# L298N.net
KiCad netlist of a schematic drawn in Altium Designer
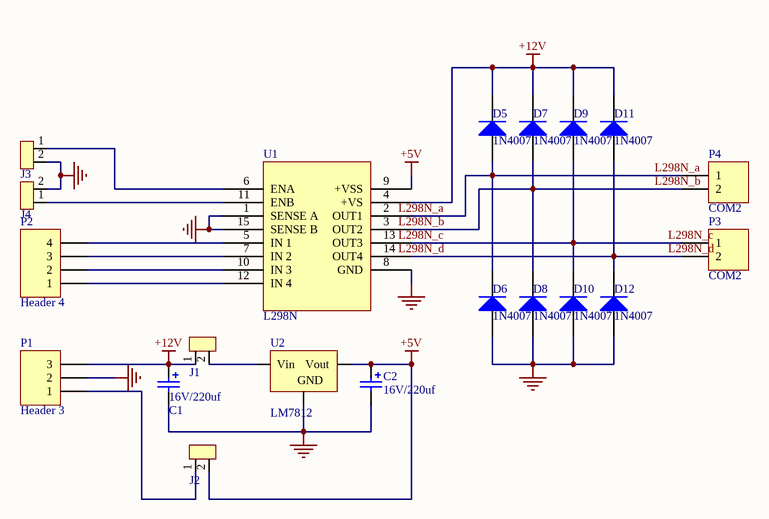
[diagram p0: L298N.SchDoc]

(export (version "E")
  (design (tool "Eeschema 10.0.6"))
  (components
    (comp (ref "C1")
      (value "16V/220uf")
      (footprint "RB5/8")
      (description "Polarized Capacitor (Radial)")
      (fields (field (name "PUBLISHER") "Altium Limited"))
      (libsource (lib "MY COM new") (part "RB"))
    )
    (comp (ref "C2")
      (value "16V/220uf")
      (footprint "RB5/8")
      (description "Polarized Capacitor (Radial)")
      (fields (field (name "PUBLISHER") "Altium Limited"))
      (libsource (lib "MY COM new") (part "RB"))
    )
    (comp (ref "D5")
      (value "1N4007")
      (footprint "Diode0.3")
      (description "1 Amp General Purpose Rectifier")
      (fields (field (name "PUBLISHER") "Altium Limited"))
      (libsource (lib "Miscellaneous Devices") (part "Diode 1N4007"))
    )
    (comp (ref "D6")
      (value "1N4007")
      (footprint "Diode0.3")
      (description "1 Amp General Purpose Rectifier")
      (fields (field (name "PUBLISHER") "Altium Limited"))
      (libsource (lib "Miscellaneous Devices") (part "Diode 1N4007"))
    )
    (comp (ref "D7")
      (value "1N4007")
      (footprint "Diode0.3")
      (description "1 Amp General Purpose Rectifier")
      (fields (field (name "PUBLISHER") "Altium Limited"))
      (libsource (lib "Miscellaneous Devices") (part "Diode 1N4007"))
    )
    (comp (ref "D8")
      (value "1N4007")
      (footprint "Diode0.3")
      (description "1 Amp General Purpose Rectifier")
      (fields (field (name "PUBLISHER") "Altium Limited"))
      (libsource (lib "Miscellaneous Devices") (part "Diode 1N4007"))
    )
    (comp (ref "D9")
      (value "1N4007")
      (footprint "Diode0.3")
      (description "1 Amp General Purpose Rectifier")
      (fields (field (name "PUBLISHER") "Altium Limited"))
      (libsource (lib "Miscellaneous Devices") (part "Diode 1N4007"))
    )
    (comp (ref "D10")
      (value "1N4007")
      (footprint "Diode0.3")
      (description "1 Amp General Purpose Rectifier")
      (fields (field (name "PUBLISHER") "Altium Limited"))
      (libsource (lib "Miscellaneous Devices") (part "Diode 1N4007"))
    )
    (comp (ref "D11")
      (value "1N4007")
      (footprint "Diode0.3")
      (description "1 Amp General Purpose Rectifier")
      (fields (field (name "PUBLISHER") "Altium Limited"))
      (libsource (lib "Miscellaneous Devices") (part "Diode 1N4007"))
    )
    (comp (ref "D12")
      (value "1N4007")
      (footprint "Diode0.3")
      (description "1 Amp General Purpose Rectifier")
      (fields (field (name "PUBLISHER") "Altium Limited"))
      (libsource (lib "Miscellaneous Devices") (part "Diode 1N4007"))
    )
    (comp (ref "J1") (value "~") (footprint "SIP2") (libsource (lib "") (part "CN2_1")))
    (comp (ref "J2") (value "CN2") (footprint "SIP2") (libsource (lib "") (part "CN2_1")))
    (comp (ref "J3") (value "~") (footprint "XH2.54-2P") (libsource (lib "") (part "CN2_2")))
    (comp (ref "J4") (value "~") (footprint "XH2.54-2P") (libsource (lib "MY COM new") (part "CN2")))
    (comp (ref "P1")
      (value "Header 3")
      (footprint "XH5.08-3P")
      (description "Header, 3-Pin")
      (fields (field (name "PUBLISHER") "Altium Limited"))
      (libsource (lib "Miscellaneous Connectors") (part "Header 3"))
    )
    (comp (ref "P2")
      (value "Header 4")
      (footprint "XH2.54-4P")
      (description "Header, 4-Pin")
      (fields (field (name "PUBLISHER") "Altium Limited"))
      (libsource (lib "Miscellaneous Connectors") (part "Header 4"))
    )
    (comp (ref "P3")
      (value "COM2")
      (footprint "XH5.08-2P")
      (description "Header, 2-Pin")
      (fields (field (name "PUBLISHER") "Altium Limited"))
      (libsource (lib "Miscellaneous Connectors") (part "Header 2"))
    )
    (comp (ref "P4")
      (value "COM2")
      (footprint "XH5.08-2P")
      (description "Header, 2-Pin")
      (fields (field (name "PUBLISHER") "Altium Limited"))
      (libsource (lib "Miscellaneous Connectors") (part "Header 2"))
    )
    (comp (ref "U1") (value "L298N") (footprint "L298N散热片") (libsource (lib "KU1") (part "L298N")))
    (comp (ref "U2")
      (value "LM7812")
      (footprint "TO-220")
      (description "Voltage Regulator")
      (fields (field (name "PUBLISHER") "Altium Limited"))
      (libsource (lib "MY COM new") (part "Voltage regulator"))
    )
  )
  (nets
    (net (code "1") (name "+5V") (class "Default")
      (node (ref "C2") (pin "1") (pinfunction "1_1") (pintype "passive"))
      (node (ref "J2") (pin "2") (pintype "passive"))
      (node (ref "U1") (pin "9") (pinfunction "+VSS_9") (pintype "passive"))
      (node (ref "U2") (pin "3") (pinfunction "Vout_3") (pintype "passive"))
    )
    (net (code "2") (name "+12V") (class "Default")
      (node (ref "C1") (pin "1") (pinfunction "1_1") (pintype "passive"))
      (node (ref "D11") (pin "2") (pinfunction "K_2") (pintype "passive"))
      (node (ref "D5") (pin "2") (pinfunction "K_2") (pintype "passive"))
      (node (ref "D7") (pin "2") (pinfunction "K_2") (pintype "passive"))
      (node (ref "D9") (pin "2") (pinfunction "K_2") (pintype "passive"))
      (node (ref "J1") (pin "1") (pintype "passive"))
      (node (ref "P1") (pin "3") (pinfunction "3_3") (pintype "passive"))
      (node (ref "U1") (pin "4") (pinfunction "+VS_4") (pintype "passive"))
    )
    (net (code "3") (name "/L298N_a") (class "Default")
      (node (ref "D5") (pin "1") (pinfunction "A_1") (pintype "passive"))
      (node (ref "D6") (pin "2") (pinfunction "K_2") (pintype "passive"))
      (node (ref "P4") (pin "1") (pinfunction "1_1") (pintype "passive"))
      (node (ref "U1") (pin "2") (pinfunction "OUT1_2") (pintype "passive"))
    )
    (net (code "4") (name "/L298N_b") (class "Default")
      (node (ref "D7") (pin "1") (pinfunction "A_1") (pintype "passive"))
      (node (ref "D8") (pin "2") (pinfunction "K_2") (pintype "passive"))
      (node (ref "P4") (pin "2") (pinfunction "2_2") (pintype "passive"))
      (node (ref "U1") (pin "3") (pinfunction "OUT2_3") (pintype "passive"))
    )
    (net (code "5") (name "/L298N_c") (class "Default")
      (node (ref "D10") (pin "2") (pinfunction "K_2") (pintype "passive"))
      (node (ref "D9") (pin "1") (pinfunction "A_1") (pintype "passive"))
      (node (ref "P3") (pin "1") (pinfunction "1_1") (pintype "passive"))
      (node (ref "U1") (pin "13") (pinfunction "OUT3_13") (pintype "passive"))
    )
    (net (code "6") (name "/L298N_d") (class "Default")
      (node (ref "D11") (pin "1") (pinfunction "A_1") (pintype "passive"))
      (node (ref "D12") (pin "2") (pinfunction "K_2") (pintype "passive"))
      (node (ref "P3") (pin "2") (pinfunction "2_2") (pintype "passive"))
      (node (ref "U1") (pin "14") (pinfunction "OUT4_14") (pintype "passive"))
    )
    (net (code "7") (name "GND") (class "Default")
      (node (ref "C1") (pin "2") (pinfunction "2_2") (pintype "passive"))
      (node (ref "C2") (pin "2") (pinfunction "2_2") (pintype "passive"))
      (node (ref "D10") (pin "1") (pinfunction "A_1") (pintype "passive"))
      (node (ref "D12") (pin "1") (pinfunction "A_1") (pintype "passive"))
      (node (ref "D6") (pin "1") (pinfunction "A_1") (pintype "passive"))
      (node (ref "D8") (pin "1") (pinfunction "A_1") (pintype "passive"))
      (node (ref "J3") (pin "2") (pintype "passive"))
      (node (ref "J4") (pin "2") (pintype "passive"))
      (node (ref "P1") (pin "2") (pinfunction "2_2") (pintype "passive"))
      (node (ref "U1") (pin "1") (pinfunction "SENSE_A_1") (pintype "passive"))
      (node (ref "U1") (pin "15") (pinfunction "SENSE_B_15") (pintype "passive"))
      (node (ref "U1") (pin "8") (pinfunction "GND_8") (pintype "passive"))
      (node (ref "U2") (pin "2") (pinfunction "GND_2") (pintype "passive"))
    )
    (net (code "8") (name "Net-(J2-Pad1)") (class "Default")
      (node (ref "J2") (pin "1") (pintype "passive"))
      (node (ref "P1") (pin "1") (pinfunction "1_1") (pintype "passive"))
    )
    (net (code "9") (name "Net-(U1-ENA)") (class "Default")
      (node (ref "J3") (pin "1") (pintype "passive"))
      (node (ref "U1") (pin "6") (pinfunction "ENA_6") (pintype "passive"))
    )
    (net (code "10") (name "Net-(U1-ENB)") (class "Default")
      (node (ref "J4") (pin "1") (pintype "passive"))
      (node (ref "U1") (pin "11") (pinfunction "ENB_11") (pintype "passive"))
    )
    (net (code "11") (name "Net-(U1-IN_1)") (class "Default")
      (node (ref "P2") (pin "4") (pinfunction "4_4") (pintype "passive"))
      (node (ref "U1") (pin "5") (pinfunction "IN_1_5") (pintype "passive"))
    )
    (net (code "12") (name "Net-(U1-IN_2)") (class "Default")
      (node (ref "P2") (pin "3") (pinfunction "3_3") (pintype "passive"))
      (node (ref "U1") (pin "7") (pinfunction "IN_2_7") (pintype "passive"))
    )
    (net (code "13") (name "Net-(U1-IN_3)") (class "Default")
      (node (ref "P2") (pin "2") (pinfunction "2_2") (pintype "passive"))
      (node (ref "U1") (pin "10") (pinfunction "IN_3_10") (pintype "passive"))
    )
    (net (code "14") (name "Net-(U1-IN_4)") (class "Default")
      (node (ref "P2") (pin "1") (pinfunction "1_1") (pintype "passive"))
      (node (ref "U1") (pin "12") (pinfunction "IN_4_12") (pintype "passive"))
    )
    (net (code "15") (name "Net-(U2-Vin)") (class "Default")
      (node (ref "J1") (pin "2") (pintype "passive"))
      (node (ref "U2") (pin "1") (pinfunction "Vin_1") (pintype "passive"))
    )
  )
)
